# 40G_ACCELEROMETER_REV_2.net
KiCad netlist of a schematic drawn in EAGLE
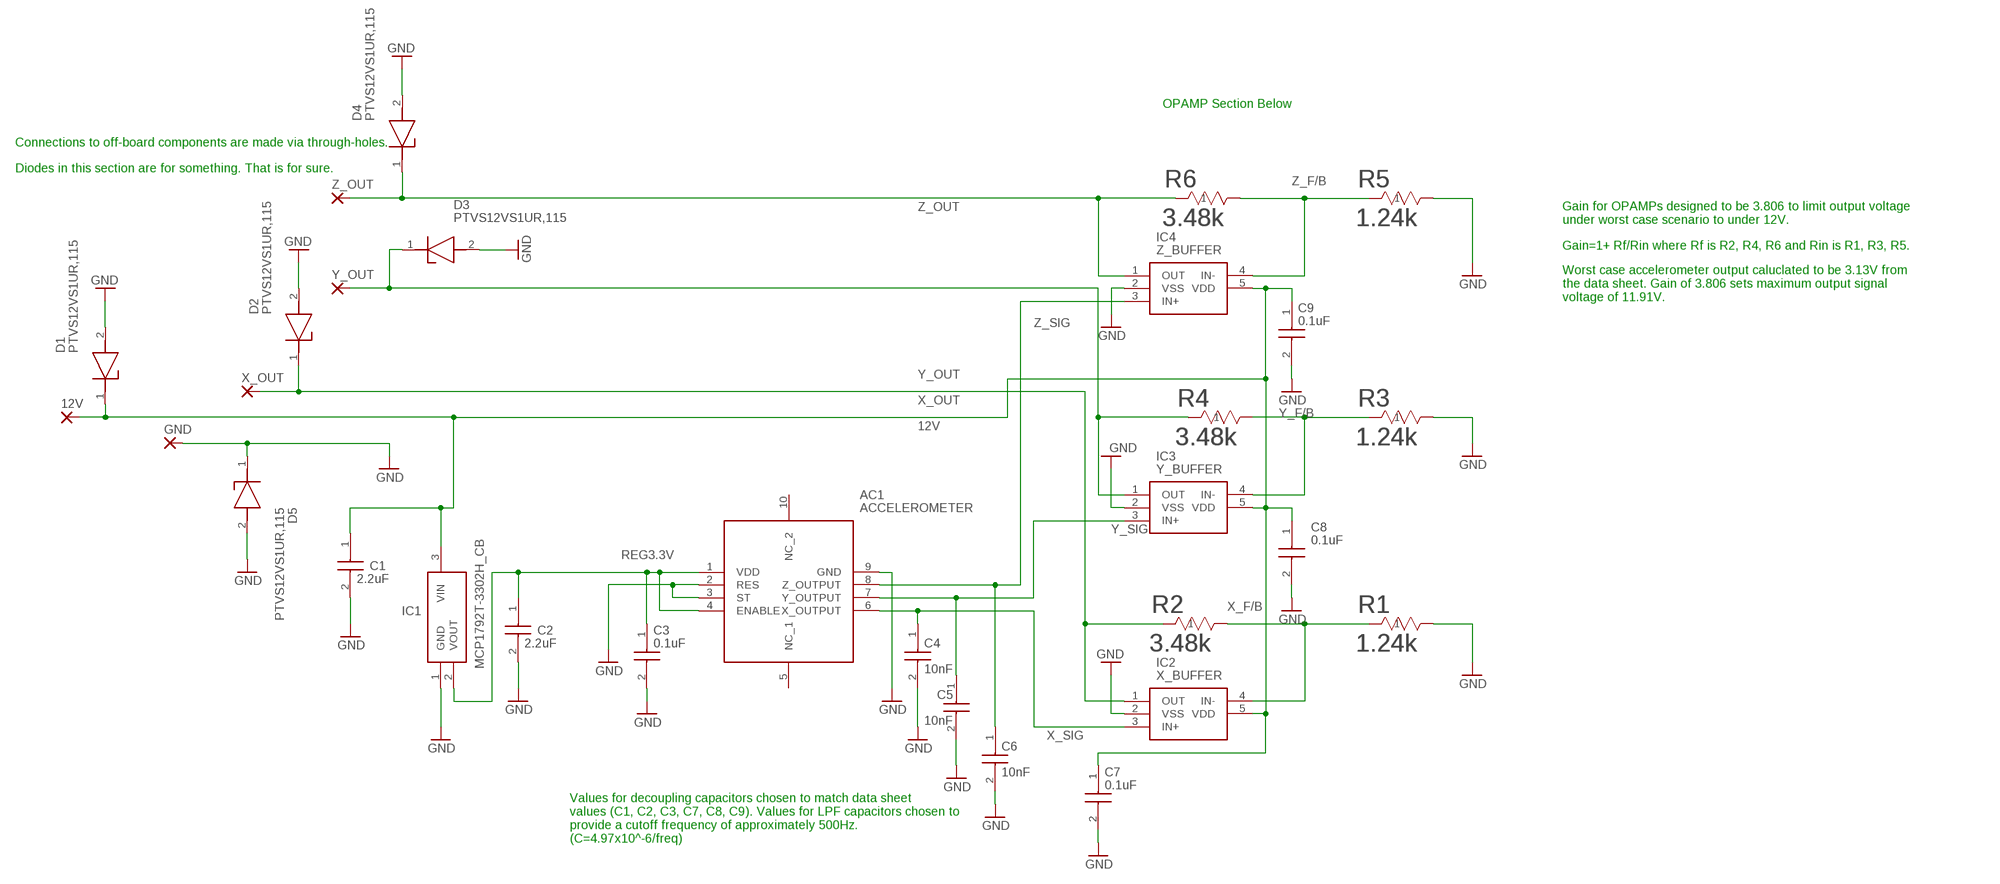
[diagram p0: schematic, sheet 1]

(export (version "E")
  (design (tool "Eeschema 10.0.6"))
  (components
    (comp (ref "12V")
      (value "2,54/1,1")
      (footprint "eagle-import:2,54_1,1")
      (libsource (lib "eagle-import") (part "2,54/1,1"))
    )
    (comp (ref "AC1")
      (value "ACCELEROMETER")
      (footprint "eagle-import:KX2201072")
      (fields
        (field (name "MANUFACTURER_PART_NUMBER") "KX220-1072")
        (field (name "MOUSER_PART_NUMBER") "912-KX220-1072")
      )
      (libsource (lib "eagle-import") (part "KX220-1072"))
    )
    (comp (ref "C1")
      (value "2.2uF")
      (footprint "eagle-import:CAPC1608X90N")
      (fields
        (field (name "MANUFACTURER_PART_NUMBER") "CGA3E1X7R0J225K080AC")
        (field (name "MOUSER_PART_NUMBER") "810-CGA3E1X7R0J225K")
      )
      (libsource (lib "eagle-import") (part "CGA3E1X7R0J225K080AC"))
    )
    (comp (ref "C2")
      (value "2.2uF")
      (footprint "eagle-import:CAPC1608X90N")
      (fields
        (field (name "MANUFACTURER_PART_NUMBER") "CGA3E1X7R0J225K080AC")
        (field (name "MOUSER_PART_NUMBER") "810-CGA3E1X7R0J225K")
      )
      (libsource (lib "eagle-import") (part "CGA3E1X7R0J225K080AC"))
    )
    (comp (ref "C3")
      (value "0.1uF")
      (footprint "eagle-import:CAPC1608X90N")
      (fields
        (field (name "MANUFACTURER_PART_NUMBER") "CGA3E2X7R1H104K080AE")
        (field (name "MOUSER_PART_NUMBER") "810-CGA3E2X7R1H104KE")
      )
      (libsource (lib "eagle-import") (part "CGA3E2X7R1H104K080AE"))
    )
    (comp (ref "C4")
      (value "10nF")
      (footprint "eagle-import:CAPC1608X90N")
      (fields
        (field (name "MANUFACTURER_PART_NUMBER") "CGA3E1C0G2A103J080AE")
        (field (name "MOUSER_PART_NUMBER") "810-CGA3E1C0G2A103J0")
      )
      (libsource (lib "eagle-import") (part "CGA3E1C0G2A103J080AE"))
    )
    (comp (ref "C5")
      (value "10nF")
      (footprint "eagle-import:CAPC1608X90N")
      (fields
        (field (name "MANUFACTURER_PART_NUMBER") "CGA3E1C0G2A103J080AE")
        (field (name "MOUSER_PART_NUMBER") "810-CGA3E1C0G2A103J0")
      )
      (libsource (lib "eagle-import") (part "CGA3E1C0G2A103J080AE"))
    )
    (comp (ref "C6")
      (value "10nF")
      (footprint "eagle-import:CAPC1608X90N")
      (fields
        (field (name "MANUFACTURER_PART_NUMBER") "CGA3E1C0G2A103J080AE")
        (field (name "MOUSER_PART_NUMBER") "810-CGA3E1C0G2A103J0")
      )
      (libsource (lib "eagle-import") (part "CGA3E1C0G2A103J080AE"))
    )
    (comp (ref "C7")
      (value "0.1uF")
      (footprint "eagle-import:CAPC1608X90N")
      (fields
        (field (name "MANUFACTURER_PART_NUMBER") "CGA3E2X7R1H104K080AE")
        (field (name "MOUSER_PART_NUMBER") "810-CGA3E2X7R1H104KE")
      )
      (libsource (lib "eagle-import") (part "CGA3E2X7R1H104K080AE"))
    )
    (comp (ref "C8")
      (value "0.1uF")
      (footprint "eagle-import:CAPC1608X90N")
      (fields
        (field (name "MANUFACTURER_PART_NUMBER") "CGA3E2X7R1H104K080AE")
        (field (name "MOUSER_PART_NUMBER") "810-CGA3E2X7R1H104KE")
      )
      (libsource (lib "eagle-import") (part "CGA3E2X7R1H104K080AE"))
    )
    (comp (ref "C9")
      (value "0.1uF")
      (footprint "eagle-import:CAPC1608X90N")
      (fields
        (field (name "MANUFACTURER_PART_NUMBER") "CGA3E2X7R1H104K080AE")
        (field (name "MOUSER_PART_NUMBER") "810-CGA3E2X7R1H104KE")
      )
      (libsource (lib "eagle-import") (part "CGA3E2X7R1H104K080AE"))
    )
    (comp (ref "D1")
      (value "PTVS12VS1UR,115")
      (footprint "eagle-import:SOD123W")
      (fields (field (name "MOUSER_PART_NUMBER") "771-PTVS12VS1UR115"))
      (libsource (lib "eagle-import") (part "PTVS12VS1UR,115"))
    )
    (comp (ref "D2")
      (value "PTVS12VS1UR,115")
      (footprint "eagle-import:SOD123W")
      (fields (field (name "MOUSER_PART_NUMBER") "771-PTVS12VS1UR115"))
      (libsource (lib "eagle-import") (part "PTVS12VS1UR,115"))
    )
    (comp (ref "D3")
      (value "PTVS12VS1UR,115")
      (footprint "eagle-import:SOD123W")
      (fields (field (name "MOUSER_PART_NUMBER") "771-PTVS12VS1UR115"))
      (libsource (lib "eagle-import") (part "PTVS12VS1UR,115"))
    )
    (comp (ref "D4")
      (value "PTVS12VS1UR,115")
      (footprint "eagle-import:SOD123W")
      (fields (field (name "MOUSER_PART_NUMBER") "771-PTVS12VS1UR115"))
      (libsource (lib "eagle-import") (part "PTVS12VS1UR,115"))
    )
    (comp (ref "D5")
      (value "PTVS12VS1UR,115")
      (footprint "eagle-import:SOD123W")
      (fields (field (name "MOUSER_PART_NUMBER") "771-PTVS12VS1UR115"))
      (libsource (lib "eagle-import") (part "PTVS12VS1UR,115"))
    )
    (comp (ref "GND")
      (value "2,54/1,1")
      (footprint "eagle-import:2,54_1,1")
      (libsource (lib "eagle-import") (part "2,54/1,1"))
    )
    (comp (ref "IC1")
      (value "MCP1792T-3302H_CB")
      (footprint "eagle-import:SOT95P255X145-3N")
      (fields
        (field (name "MANUFACTURER_PART_NUMBER") "MCP1792T-3302H/CB")
        (field (name "MOUSER_PART_NUMBER") "579-MCP1792T-3302HCB")
      )
      (libsource (lib "eagle-import") (part "MCP1792T-3302H_CB"))
    )
    (comp (ref "IC2")
      (value "X_BUFFER")
      (footprint "eagle-import:SOT95P275X110-5N")
      (fields
        (field (name "MANUFACTURER_PART_NUMBER") "NCS21911SN2T1G")
        (field (name "MOUSER_PART_NUMBER") "863-NCS21911SN2T1G")
      )
      (libsource (lib "eagle-import") (part "NCS21911SN2T1G"))
    )
    (comp (ref "IC3")
      (value "Y_BUFFER")
      (footprint "eagle-import:SOT95P275X110-5N")
      (fields
        (field (name "MANUFACTURER_PART_NUMBER") "NCS21911SN2T1G")
        (field (name "MOUSER_PART_NUMBER") "863-NCS21911SN2T1G")
      )
      (libsource (lib "eagle-import") (part "NCS21911SN2T1G"))
    )
    (comp (ref "IC4")
      (value "Z_BUFFER")
      (footprint "eagle-import:SOT95P275X110-5N")
      (fields
        (field (name "MANUFACTURER_PART_NUMBER") "NCS21911SN2T1G")
        (field (name "MOUSER_PART_NUMBER") "863-NCS21911SN2T1G")
      )
      (libsource (lib "eagle-import") (part "NCS21911SN2T1G"))
    )
    (comp (ref "R1")
      (value "1.24k")
      (footprint "eagle-import:RES_TNPW0402_VIS")
      (fields
        (field (name "MANUFACTURER_PART_NUMBER") "TNPW04021K24BEED")
        (field (name "COPYRIGHT") "Copyright (C) 2022 Ultra Librarian. All rights reserved.")
      )
      (libsource (lib "eagle-import") (part "TNPW04021K24BEED"))
    )
    (comp (ref "R2")
      (value "3.48k")
      (footprint "eagle-import:RES_TNPW0402_VIS")
      (fields
        (field (name "MANUFACTURER_PART_NUMBER") "TNPW04023K48BEED")
        (field (name "COPYRIGHT") "Copyright (C) 2022 Ultra Librarian. All rights reserved.")
      )
      (libsource (lib "eagle-import") (part "TNPW04023K48BEED"))
    )
    (comp (ref "R3")
      (value "1.24k")
      (footprint "eagle-import:RES_TNPW0402_VIS")
      (fields
        (field (name "MANUFACTURER_PART_NUMBER") "TNPW04021K24BEED")
        (field (name "COPYRIGHT") "Copyright (C) 2022 Ultra Librarian. All rights reserved.")
      )
      (libsource (lib "eagle-import") (part "TNPW04021K24BEED"))
    )
    (comp (ref "R4")
      (value "3.48k")
      (footprint "eagle-import:RES_TNPW0402_VIS")
      (fields
        (field (name "MANUFACTURER_PART_NUMBER") "TNPW04023K48BEED")
        (field (name "COPYRIGHT") "Copyright (C) 2022 Ultra Librarian. All rights reserved.")
      )
      (libsource (lib "eagle-import") (part "TNPW04023K48BEED"))
    )
    (comp (ref "R5")
      (value "1.24k")
      (footprint "eagle-import:RES_TNPW0402_VIS")
      (fields
        (field (name "MANUFACTURER_PART_NUMBER") "TNPW04021K24BEED")
        (field (name "COPYRIGHT") "Copyright (C) 2022 Ultra Librarian. All rights reserved.")
      )
      (libsource (lib "eagle-import") (part "TNPW04021K24BEED"))
    )
    (comp (ref "R6")
      (value "3.48k")
      (footprint "eagle-import:RES_TNPW0402_VIS")
      (fields
        (field (name "MANUFACTURER_PART_NUMBER") "TNPW04023K48BEED")
        (field (name "COPYRIGHT") "Copyright (C) 2022 Ultra Librarian. All rights reserved.")
      )
      (libsource (lib "eagle-import") (part "TNPW04023K48BEED"))
    )
    (comp (ref "X_OUT")
      (value "2,54/1,1")
      (footprint "eagle-import:2,54_1,1")
      (libsource (lib "eagle-import") (part "2,54/1,1"))
    )
    (comp (ref "Y_OUT")
      (value "2,54/1,1")
      (footprint "eagle-import:2,54_1,1")
      (libsource (lib "eagle-import") (part "2,54/1,1"))
    )
    (comp (ref "Z_OUT")
      (value "2,54/1,1")
      (footprint "eagle-import:2,54_1,1")
      (libsource (lib "eagle-import") (part "2,54/1,1"))
    )
  )
  (nets
    (net (code "1") (name "/12V") (class "Default")
      (node (ref "12V") (pin "1") (pinfunction "P_1") (pintype "passive"))
      (node (ref "C1") (pin "1") (pinfunction "1_1") (pintype "bidirectional"))
      (node (ref "C7") (pin "1") (pinfunction "1_1") (pintype "bidirectional"))
      (node (ref "C8") (pin "1") (pinfunction "1_1") (pintype "bidirectional"))
      (node (ref "C9") (pin "1") (pinfunction "1_1") (pintype "bidirectional"))
      (node (ref "D1") (pin "1") (pinfunction "K_1") (pintype "bidirectional"))
      (node (ref "IC1") (pin "3") (pinfunction "VIN_3") (pintype "bidirectional"))
      (node (ref "IC2") (pin "5") (pinfunction "VDD_5") (pintype "bidirectional"))
      (node (ref "IC3") (pin "5") (pinfunction "VDD_5") (pintype "bidirectional"))
      (node (ref "IC4") (pin "5") (pinfunction "VDD_5") (pintype "bidirectional"))
    )
    (net (code "2") (name "/REG3.3V") (class "Default")
      (node (ref "AC1") (pin "1") (pinfunction "VDD_1") (pintype "bidirectional"))
      (node (ref "AC1") (pin "4") (pinfunction "ENABLE_4") (pintype "bidirectional"))
      (node (ref "C2") (pin "1") (pinfunction "1_1") (pintype "bidirectional"))
      (node (ref "C3") (pin "1") (pinfunction "1_1") (pintype "bidirectional"))
      (node (ref "IC1") (pin "2") (pinfunction "VOUT_2") (pintype "bidirectional"))
    )
    (net (code "3") (name "/X_F{slash}B") (class "Default")
      (node (ref "IC2") (pin "4") (pinfunction "IN-_4") (pintype "bidirectional"))
      (node (ref "R1") (pin "1") (pinfunction "1_1") (pintype "passive"))
      (node (ref "R2") (pin "2") (pinfunction "2_2") (pintype "passive"))
    )
    (net (code "4") (name "/X_OUT") (class "Default")
      (node (ref "D2") (pin "1") (pinfunction "K_1") (pintype "bidirectional"))
      (node (ref "IC2") (pin "1") (pinfunction "OUT_1") (pintype "bidirectional"))
      (node (ref "R2") (pin "1") (pinfunction "1_1") (pintype "passive"))
      (node (ref "X_OUT") (pin "1") (pinfunction "P_1") (pintype "passive"))
    )
    (net (code "5") (name "/X_SIG") (class "Default")
      (node (ref "AC1") (pin "6") (pinfunction "X_OUTPUT_6") (pintype "bidirectional"))
      (node (ref "C4") (pin "1") (pinfunction "1_1") (pintype "bidirectional"))
      (node (ref "IC2") (pin "3") (pinfunction "IN+_3") (pintype "bidirectional"))
    )
    (net (code "6") (name "/Y_F{slash}B") (class "Default")
      (node (ref "IC3") (pin "4") (pinfunction "IN-_4") (pintype "bidirectional"))
      (node (ref "R3") (pin "1") (pinfunction "1_1") (pintype "passive"))
      (node (ref "R4") (pin "2") (pinfunction "2_2") (pintype "passive"))
    )
    (net (code "7") (name "/Y_OUT") (class "Default")
      (node (ref "D3") (pin "1") (pinfunction "K_1") (pintype "bidirectional"))
      (node (ref "IC3") (pin "1") (pinfunction "OUT_1") (pintype "bidirectional"))
      (node (ref "R4") (pin "1") (pinfunction "1_1") (pintype "passive"))
      (node (ref "Y_OUT") (pin "1") (pinfunction "P_1") (pintype "passive"))
    )
    (net (code "8") (name "/Y_SIG") (class "Default")
      (node (ref "AC1") (pin "7") (pinfunction "Y_OUTPUT_7") (pintype "bidirectional"))
      (node (ref "C5") (pin "1") (pinfunction "1_1") (pintype "bidirectional"))
      (node (ref "IC3") (pin "3") (pinfunction "IN+_3") (pintype "bidirectional"))
    )
    (net (code "9") (name "/Z_F{slash}B") (class "Default")
      (node (ref "IC4") (pin "4") (pinfunction "IN-_4") (pintype "bidirectional"))
      (node (ref "R5") (pin "1") (pinfunction "1_1") (pintype "passive"))
      (node (ref "R6") (pin "2") (pinfunction "2_2") (pintype "passive"))
    )
    (net (code "10") (name "/Z_OUT") (class "Default")
      (node (ref "D4") (pin "1") (pinfunction "K_1") (pintype "bidirectional"))
      (node (ref "IC4") (pin "1") (pinfunction "OUT_1") (pintype "bidirectional"))
      (node (ref "R6") (pin "1") (pinfunction "1_1") (pintype "passive"))
      (node (ref "Z_OUT") (pin "1") (pinfunction "P_1") (pintype "passive"))
    )
    (net (code "11") (name "/Z_SIG") (class "Default")
      (node (ref "AC1") (pin "8") (pinfunction "Z_OUTPUT_8") (pintype "bidirectional"))
      (node (ref "C6") (pin "1") (pinfunction "1_1") (pintype "bidirectional"))
      (node (ref "IC4") (pin "3") (pinfunction "IN+_3") (pintype "bidirectional"))
    )
    (net (code "12") (name "GND") (class "Default")
      (node (ref "AC1") (pin "2") (pinfunction "RES_2") (pintype "bidirectional"))
      (node (ref "AC1") (pin "3") (pinfunction "ST_3") (pintype "bidirectional"))
      (node (ref "AC1") (pin "9") (pinfunction "GND_9") (pintype "bidirectional"))
      (node (ref "C1") (pin "2") (pinfunction "2_2") (pintype "bidirectional"))
      (node (ref "C2") (pin "2") (pinfunction "2_2") (pintype "bidirectional"))
      (node (ref "C3") (pin "2") (pinfunction "2_2") (pintype "bidirectional"))
      (node (ref "C4") (pin "2") (pinfunction "2_2") (pintype "bidirectional"))
      (node (ref "C5") (pin "2") (pinfunction "2_2") (pintype "bidirectional"))
      (node (ref "C6") (pin "2") (pinfunction "2_2") (pintype "bidirectional"))
      (node (ref "C7") (pin "2") (pinfunction "2_2") (pintype "bidirectional"))
      (node (ref "C8") (pin "2") (pinfunction "2_2") (pintype "bidirectional"))
      (node (ref "C9") (pin "2") (pinfunction "2_2") (pintype "bidirectional"))
      (node (ref "D1") (pin "2") (pinfunction "A_2") (pintype "bidirectional"))
      (node (ref "D2") (pin "2") (pinfunction "A_2") (pintype "bidirectional"))
      (node (ref "D3") (pin "2") (pinfunction "A_2") (pintype "bidirectional"))
      (node (ref "D4") (pin "2") (pinfunction "A_2") (pintype "bidirectional"))
      (node (ref "D5") (pin "1") (pinfunction "K_1") (pintype "bidirectional"))
      (node (ref "D5") (pin "2") (pinfunction "A_2") (pintype "bidirectional"))
      (node (ref "GND") (pin "1") (pinfunction "P_1") (pintype "passive"))
      (node (ref "IC1") (pin "1") (pinfunction "GND_1") (pintype "bidirectional"))
      (node (ref "IC2") (pin "2") (pinfunction "VSS_2") (pintype "bidirectional"))
      (node (ref "IC3") (pin "2") (pinfunction "VSS_2") (pintype "bidirectional"))
      (node (ref "IC4") (pin "2") (pinfunction "VSS_2") (pintype "bidirectional"))
      (node (ref "R1") (pin "2") (pinfunction "2_2") (pintype "passive"))
      (node (ref "R3") (pin "2") (pinfunction "2_2") (pintype "passive"))
      (node (ref "R5") (pin "2") (pinfunction "2_2") (pintype "passive"))
    )
    (net (code "13") (name "unconnected-(AC1-NC_1-Pad5)") (class "Default")
      (node (ref "AC1") (pin "5") (pinfunction "NC_1_5") (pintype "bidirectional"))
    )
    (net (code "14") (name "unconnected-(AC1-NC_2-Pad10)") (class "Default")
      (node (ref "AC1") (pin "10") (pinfunction "NC_2_10") (pintype "bidirectional"))
    )
  )
)
